# controllercap.net
KiCad netlist of a schematic drawn in EAGLE
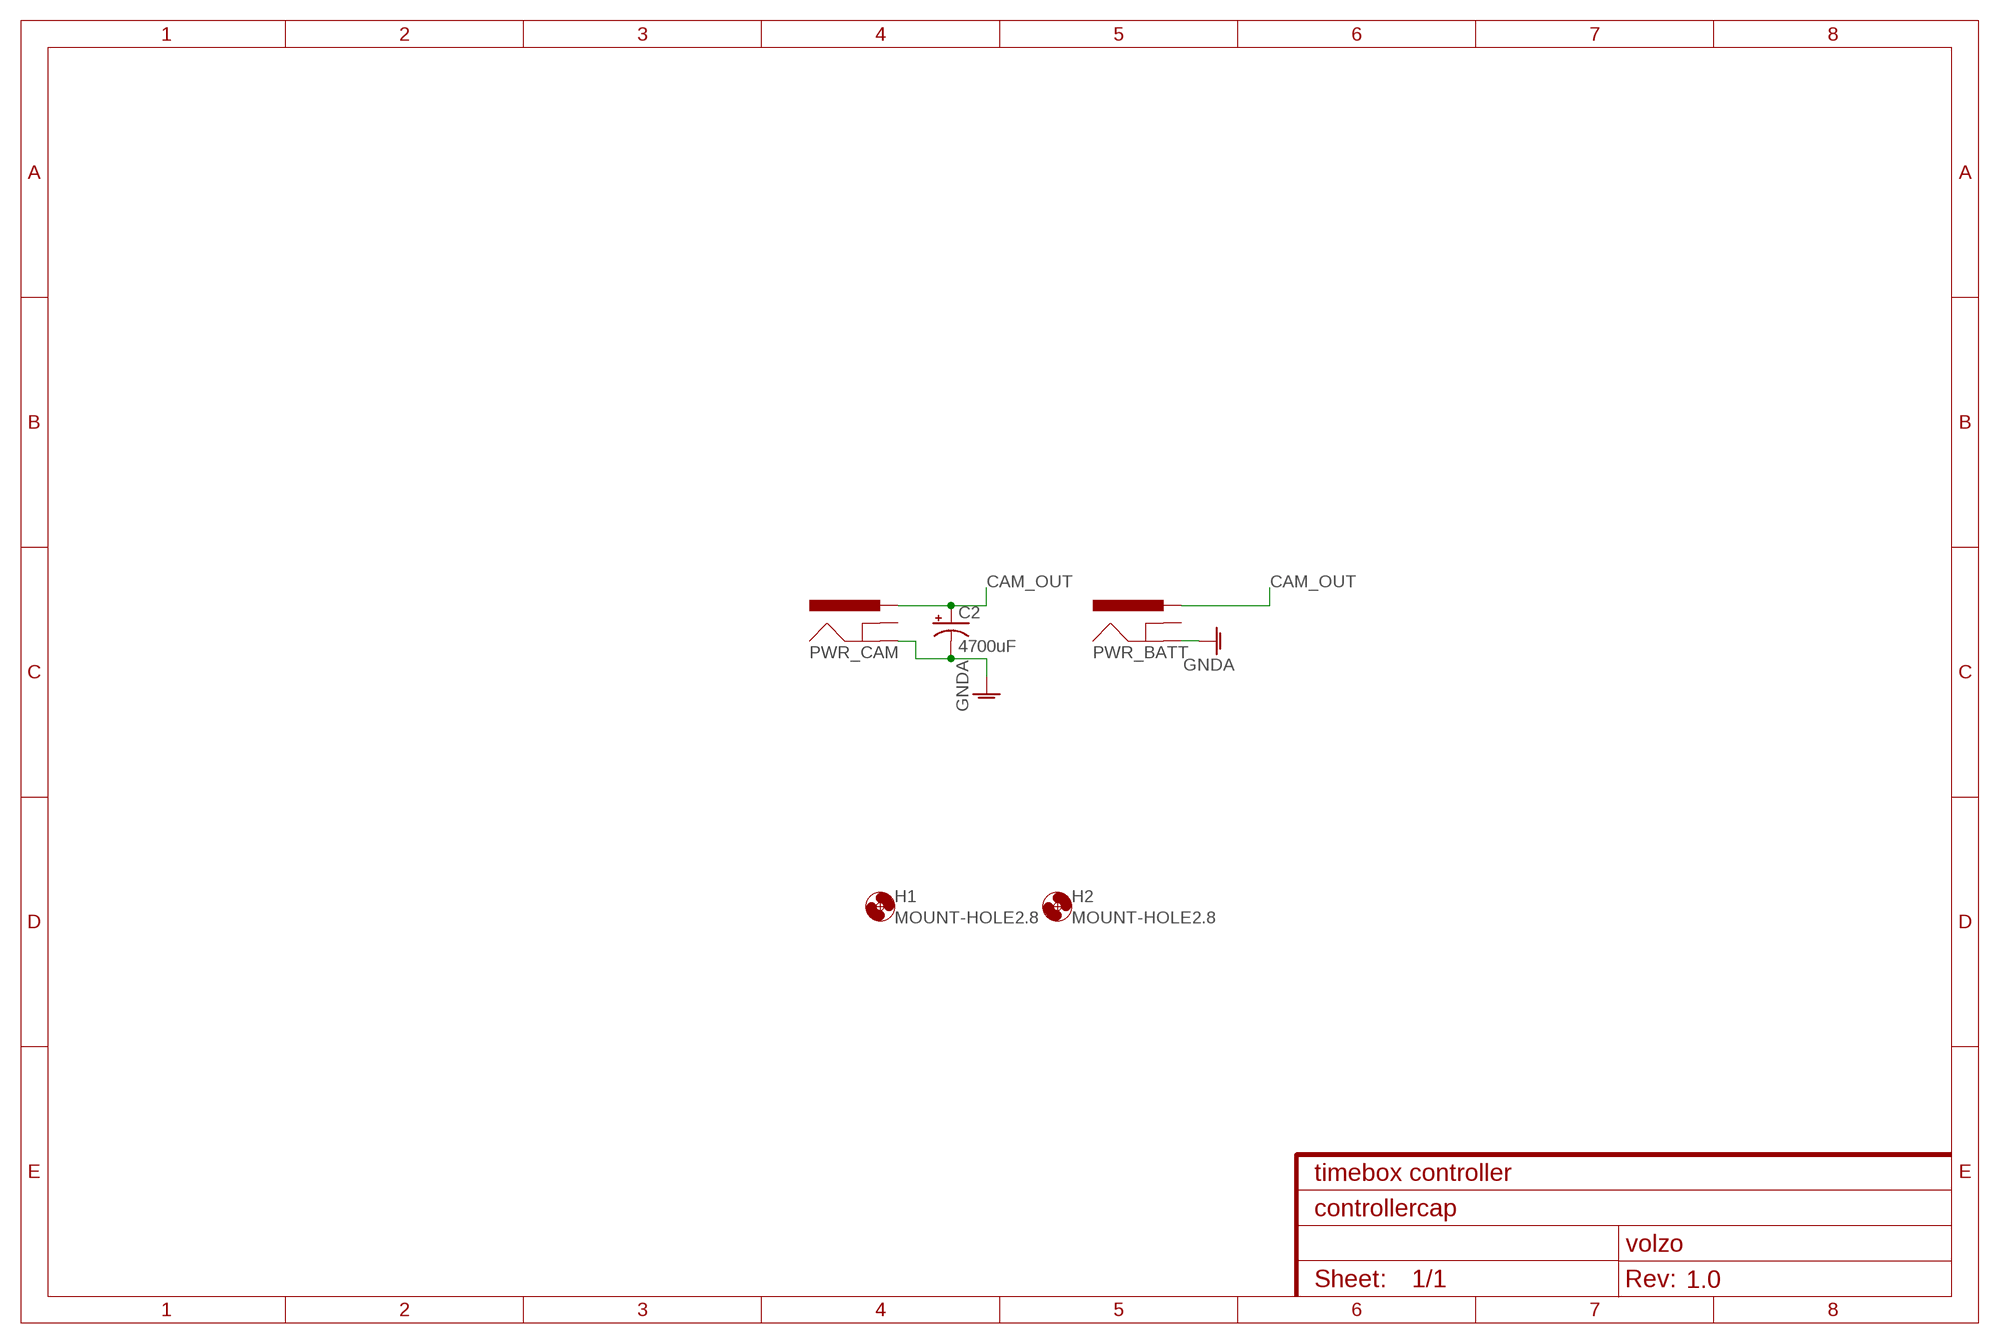
[diagram p0: schematic, sheet 1]

(export (version "E")
  (design (tool "Eeschema 10.0.6"))
  (components
    (comp (ref "C2")
      (value "4700uF")
      (footprint "eagle-import:CPOL-RADIAL-1000UF-63V")
      (libsource (lib "eagle-import") (part "CAP_POLPTH3"))
    )
    (comp (ref "H1")
      (value "MOUNT-HOLE2.8")
      (footprint "eagle-import:2,8")
      (libsource (lib "eagle-import") (part "MOUNT-HOLE2.8"))
    )
    (comp (ref "H2")
      (value "MOUNT-HOLE2.8")
      (footprint "eagle-import:2,8")
      (libsource (lib "eagle-import") (part "MOUNT-HOLE2.8"))
    )
    (comp (ref "PWR_BATT")
      (value "POWER_JACKPTH_BREAD")
      (footprint "eagle-import:POWER_JACK_PTH_BREAD")
      (libsource (lib "eagle-import") (part "POWER_JACKPTH_BREAD"))
    )
    (comp (ref "PWR_CAM")
      (value "POWER_JACKPTH_BREAD")
      (footprint "eagle-import:POWER_JACK_PTH_BREAD")
      (libsource (lib "eagle-import") (part "POWER_JACKPTH_BREAD"))
    )
  )
  (nets
    (net (code "1") (name "/CAM_OUT") (class "Default")
      (node (ref "C2") (pin "1") (pinfunction "+_1") (pintype "passive"))
      (node (ref "PWR_BATT") (pin "PWR") (pinfunction "PWR_PWR") (pintype "bidirectional"))
      (node (ref "PWR_CAM") (pin "PWR") (pinfunction "PWR_PWR") (pintype "bidirectional"))
    )
    (net (code "2") (name "GNDA") (class "Default")
      (node (ref "C2") (pin "2") (pinfunction "-_2") (pintype "passive"))
      (node (ref "PWR_BATT") (pin "GND") (pinfunction "GND_GND") (pintype "bidirectional"))
      (node (ref "PWR_CAM") (pin "GND") (pinfunction "GND_GND") (pintype "bidirectional"))
    )
    (net (code "3") (name "unconnected-(PWR_BATT-PadGNDBREAK)") (class "Default")
      (node (ref "PWR_BATT") (pin "GNDBREAK") (pinfunction "GNDBREAK_GNDBREAK") (pintype "bidirectional"))
    )
    (net (code "4") (name "unconnected-(PWR_CAM-PadGNDBREAK)") (class "Default")
      (node (ref "PWR_CAM") (pin "GNDBREAK") (pinfunction "GNDBREAK_GNDBREAK") (pintype "bidirectional"))
    )
  )
)
